# MBoardConnect.net
KiCad netlist of a schematic drawn in Altium Designer
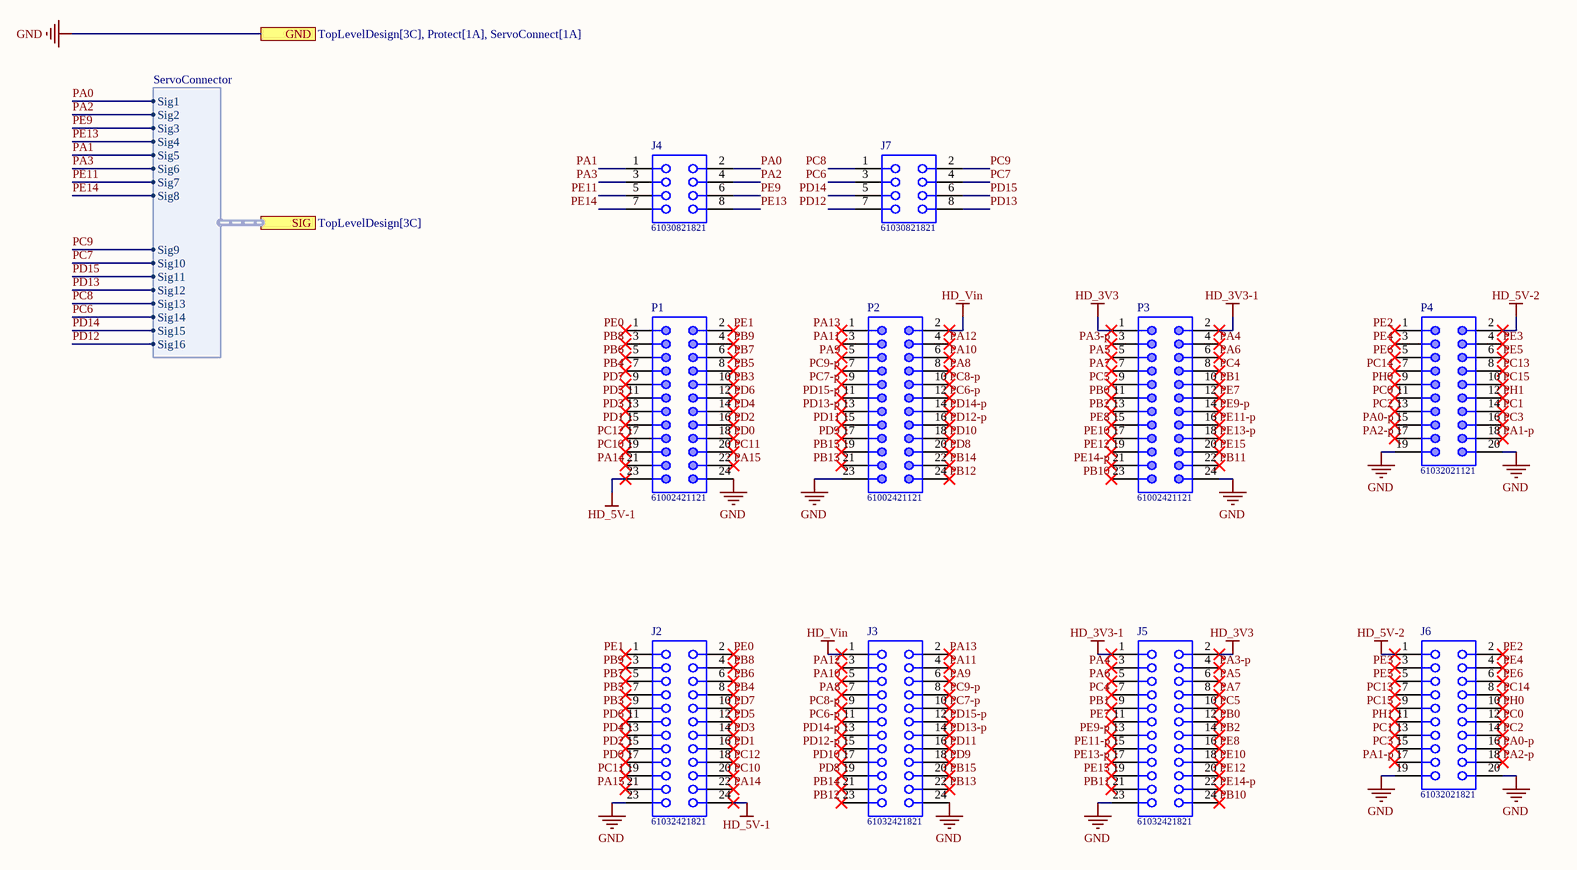
[diagram p0: MBoardConnect.SchDoc]

(export (version "E")
  (design (tool "Eeschema 10.0.6"))
  (components
    (comp (ref "J2")
      (value "61032421821")
      (footprint "61032421821")
      (description "WR-PHD Socket Header, SMT, pitch 2.54mm, Dual Row, Vertical, 24p")
      (fields (field (name "MANUFACTURER") "Wurth Elektronik"))
      (libsource (lib "Tin Tran") (part "613024243121"))
    )
    (comp (ref "J3")
      (value "61032421821")
      (footprint "61032421821")
      (description "WR-PHD Socket Header, SMT, pitch 2.54mm, Dual Row, Vertical, 24p")
      (fields (field (name "MANUFACTURER") "Wurth Elektronik"))
      (libsource (lib "Tin Tran") (part "613024243121"))
    )
    (comp (ref "J4")
      (value "61030821821")
      (footprint "61030821821")
      (description "WR-PHD Socket Header, SMT, pitch 2.54mm, Dual Row, Vertical, 8p")
      (fields (field (name "MANUFACTURER") "Wurth Elektronik"))
      (libsource (lib "Tin Tran") (part "613008243121"))
    )
    (comp (ref "J5")
      (value "61032421821")
      (footprint "61032421821")
      (description "WR-PHD Socket Header, SMT, pitch 2.54mm, Dual Row, Vertical, 24p")
      (fields (field (name "MANUFACTURER") "Wurth Elektronik"))
      (libsource (lib "Tin Tran") (part "613024243121"))
    )
    (comp (ref "J6")
      (value "61032021821")
      (footprint "61032021821")
      (description "WR-PHD Socket Header, SMT, pitch 2.54mm, Dual Row, Vertical, 20p")
      (fields (field (name "MANUFACTURER") "Wurth Elektronik"))
      (libsource (lib "Tin Tran") (part "613020243121"))
    )
    (comp (ref "J7")
      (value "61030821821")
      (footprint "61030821821")
      (description "WR-PHD Socket Header, SMT, pitch 2.54mm, Dual Row, Vertical, 8p")
      (fields (field (name "MANUFACTURER") "Wurth Elektronik"))
      (libsource (lib "Tin Tran") (part "613008243121"))
    )
    (comp (ref "P1")
      (value "61002421121")
      (footprint "61002421121")
      (description "WR-PHD Pin Header, SMT, pitch 2.54mm, Dual Row, Vertical, 24p")
      (fields (field (name "MANUFACTURER") "Wurth Elektronik"))
      (libsource (lib "Tin Tran") (part "61302421121"))
    )
    (comp (ref "P2")
      (value "61002421121")
      (footprint "61002421121")
      (description "WR-PHD Pin Header, SMT, pitch 2.54mm, Dual Row, Vertical, 24p")
      (fields (field (name "MANUFACTURER") "Wurth Elektronik"))
      (libsource (lib "Tin Tran") (part "61302421121"))
    )
    (comp (ref "P3")
      (value "61002421121")
      (footprint "61002421121")
      (description "WR-PHD Pin Header, SMT, pitch 2.54mm, Dual Row, Vertical, 24p")
      (fields (field (name "MANUFACTURER") "Wurth Elektronik"))
      (libsource (lib "Tin Tran") (part "61302421121"))
    )
    (comp (ref "P4")
      (value "61032021121")
      (footprint "61032021121")
      (description "WR-PHD Pin Header, SMT, pitch 2.54mm, Dual Row, Vertical, 20p")
      (fields (field (name "MANUFACTURER") "Wurth Elektronik"))
      (libsource (lib "Tin Tran") (part "61302021121"))
    )
  )
  (nets
    (net (code "2") (name "/PA0") (class "Default")
      (node (ref "J4") (pin "2") (pinfunction "2_2") (pintype "passive"))
    )
    (net (code "3") (name "/PA0-p") (class "Default")
      (node (ref "J6") (pin "16") (pinfunction "16_16") (pintype "passive"))
      (node (ref "P4") (pin "15") (pinfunction "15_15") (pintype "passive"))
    )
    (net (code "4") (name "/PA1") (class "Default")
      (node (ref "J4") (pin "1") (pinfunction "1_1") (pintype "passive"))
    )
    (net (code "5") (name "/PA1-p") (class "Default")
      (node (ref "J6") (pin "17") (pinfunction "17_17") (pintype "passive"))
      (node (ref "P4") (pin "18") (pinfunction "18_18") (pintype "passive"))
    )
    (net (code "6") (name "/PA2") (class "Default")
      (node (ref "J4") (pin "4") (pinfunction "4_4") (pintype "passive"))
    )
    (net (code "7") (name "/PA2-p") (class "Default")
      (node (ref "J6") (pin "18") (pinfunction "18_18") (pintype "passive"))
      (node (ref "P4") (pin "17") (pinfunction "17_17") (pintype "passive"))
    )
    (net (code "8") (name "/PA3") (class "Default")
      (node (ref "J4") (pin "3") (pinfunction "3_3") (pintype "passive"))
    )
    (net (code "9") (name "/PA3-p") (class "Default")
      (node (ref "J5") (pin "4") (pinfunction "4_4") (pintype "passive"))
      (node (ref "P3") (pin "3") (pinfunction "3_3") (pintype "passive"))
    )
    (net (code "10") (name "/PA4") (class "Default")
      (node (ref "J5") (pin "3") (pinfunction "3_3") (pintype "passive"))
      (node (ref "P3") (pin "4") (pinfunction "4_4") (pintype "passive"))
    )
    (net (code "11") (name "/PA5") (class "Default")
      (node (ref "J5") (pin "6") (pinfunction "6_6") (pintype "passive"))
      (node (ref "P3") (pin "5") (pinfunction "5_5") (pintype "passive"))
    )
    (net (code "12") (name "/PA6") (class "Default")
      (node (ref "J5") (pin "5") (pinfunction "5_5") (pintype "passive"))
      (node (ref "P3") (pin "6") (pinfunction "6_6") (pintype "passive"))
    )
    (net (code "13") (name "/PA7") (class "Default")
      (node (ref "J5") (pin "8") (pinfunction "8_8") (pintype "passive"))
      (node (ref "P3") (pin "7") (pinfunction "7_7") (pintype "passive"))
    )
    (net (code "14") (name "/PA8") (class "Default")
      (node (ref "J3") (pin "7") (pinfunction "7_7") (pintype "passive"))
      (node (ref "P2") (pin "8") (pinfunction "8_8") (pintype "passive"))
    )
    (net (code "15") (name "/PA9") (class "Default")
      (node (ref "J3") (pin "6") (pinfunction "6_6") (pintype "passive"))
      (node (ref "P2") (pin "5") (pinfunction "5_5") (pintype "passive"))
    )
    (net (code "16") (name "/PA10") (class "Default")
      (node (ref "J3") (pin "5") (pinfunction "5_5") (pintype "passive"))
      (node (ref "P2") (pin "6") (pinfunction "6_6") (pintype "passive"))
    )
    (net (code "17") (name "/PA11") (class "Default")
      (node (ref "J3") (pin "4") (pinfunction "4_4") (pintype "passive"))
      (node (ref "P2") (pin "3") (pinfunction "3_3") (pintype "passive"))
    )
    (net (code "18") (name "/PA12") (class "Default")
      (node (ref "J3") (pin "3") (pinfunction "3_3") (pintype "passive"))
      (node (ref "P2") (pin "4") (pinfunction "4_4") (pintype "passive"))
    )
    (net (code "19") (name "/PA13") (class "Default")
      (node (ref "J3") (pin "2") (pinfunction "2_2") (pintype "passive"))
      (node (ref "P2") (pin "1") (pinfunction "1_1") (pintype "passive"))
    )
    (net (code "20") (name "/PA14") (class "Default")
      (node (ref "J2") (pin "22") (pinfunction "22_22") (pintype "passive"))
      (node (ref "P1") (pin "21") (pinfunction "21_21") (pintype "passive"))
    )
    (net (code "21") (name "/PA15") (class "Default")
      (node (ref "J2") (pin "21") (pinfunction "21_21") (pintype "passive"))
      (node (ref "P1") (pin "22") (pinfunction "22_22") (pintype "passive"))
    )
    (net (code "22") (name "/PB0") (class "Default")
      (node (ref "J5") (pin "12") (pinfunction "12_12") (pintype "passive"))
      (node (ref "P3") (pin "11") (pinfunction "11_11") (pintype "passive"))
    )
    (net (code "23") (name "/PB1") (class "Default")
      (node (ref "J5") (pin "9") (pinfunction "9_9") (pintype "passive"))
      (node (ref "P3") (pin "10") (pinfunction "10_10") (pintype "passive"))
    )
    (net (code "24") (name "/PB2") (class "Default")
      (node (ref "J5") (pin "14") (pinfunction "14_14") (pintype "passive"))
      (node (ref "P3") (pin "13") (pinfunction "13_13") (pintype "passive"))
    )
    (net (code "25") (name "/PB3") (class "Default")
      (node (ref "J2") (pin "9") (pinfunction "9_9") (pintype "passive"))
      (node (ref "P1") (pin "10") (pinfunction "10_10") (pintype "passive"))
    )
    (net (code "26") (name "/PB4") (class "Default")
      (node (ref "J2") (pin "8") (pinfunction "8_8") (pintype "passive"))
      (node (ref "P1") (pin "7") (pinfunction "7_7") (pintype "passive"))
    )
    (net (code "27") (name "/PB5") (class "Default")
      (node (ref "J2") (pin "7") (pinfunction "7_7") (pintype "passive"))
      (node (ref "P1") (pin "8") (pinfunction "8_8") (pintype "passive"))
    )
    (net (code "28") (name "/PB6") (class "Default")
      (node (ref "J2") (pin "6") (pinfunction "6_6") (pintype "passive"))
      (node (ref "P1") (pin "5") (pinfunction "5_5") (pintype "passive"))
    )
    (net (code "29") (name "/PB7") (class "Default")
      (node (ref "J2") (pin "5") (pinfunction "5_5") (pintype "passive"))
      (node (ref "P1") (pin "6") (pinfunction "6_6") (pintype "passive"))
    )
    (net (code "30") (name "/PB8") (class "Default")
      (node (ref "J2") (pin "4") (pinfunction "4_4") (pintype "passive"))
      (node (ref "P1") (pin "3") (pinfunction "3_3") (pintype "passive"))
    )
    (net (code "31") (name "/PB9") (class "Default")
      (node (ref "J2") (pin "3") (pinfunction "3_3") (pintype "passive"))
      (node (ref "P1") (pin "4") (pinfunction "4_4") (pintype "passive"))
    )
    (net (code "32") (name "/PB10") (class "Default")
      (node (ref "J5") (pin "24") (pinfunction "24_24") (pintype "passive"))
      (node (ref "P3") (pin "23") (pinfunction "23_23") (pintype "passive"))
    )
    (net (code "33") (name "/PB11") (class "Default")
      (node (ref "J5") (pin "21") (pinfunction "21_21") (pintype "passive"))
      (node (ref "P3") (pin "22") (pinfunction "22_22") (pintype "passive"))
    )
    (net (code "34") (name "/PB12") (class "Default")
      (node (ref "J3") (pin "23") (pinfunction "23_23") (pintype "passive"))
      (node (ref "P2") (pin "24") (pinfunction "24_24") (pintype "passive"))
    )
    (net (code "35") (name "/PB13") (class "Default")
      (node (ref "J3") (pin "22") (pinfunction "22_22") (pintype "passive"))
      (node (ref "P2") (pin "21") (pinfunction "21_21") (pintype "passive"))
    )
    (net (code "36") (name "/PB14") (class "Default")
      (node (ref "J3") (pin "21") (pinfunction "21_21") (pintype "passive"))
      (node (ref "P2") (pin "22") (pinfunction "22_22") (pintype "passive"))
    )
    (net (code "37") (name "/PB15") (class "Default")
      (node (ref "J3") (pin "20") (pinfunction "20_20") (pintype "passive"))
      (node (ref "P2") (pin "19") (pinfunction "19_19") (pintype "passive"))
    )
    (net (code "38") (name "/PC0") (class "Default")
      (node (ref "J6") (pin "12") (pinfunction "12_12") (pintype "passive"))
      (node (ref "P4") (pin "11") (pinfunction "11_11") (pintype "passive"))
    )
    (net (code "39") (name "/PC1") (class "Default")
      (node (ref "J6") (pin "13") (pinfunction "13_13") (pintype "passive"))
      (node (ref "P4") (pin "14") (pinfunction "14_14") (pintype "passive"))
    )
    (net (code "40") (name "/PC2") (class "Default")
      (node (ref "J6") (pin "14") (pinfunction "14_14") (pintype "passive"))
      (node (ref "P4") (pin "13") (pinfunction "13_13") (pintype "passive"))
    )
    (net (code "41") (name "/PC3") (class "Default")
      (node (ref "J6") (pin "15") (pinfunction "15_15") (pintype "passive"))
      (node (ref "P4") (pin "16") (pinfunction "16_16") (pintype "passive"))
    )
    (net (code "42") (name "/PC4") (class "Default")
      (node (ref "J5") (pin "7") (pinfunction "7_7") (pintype "passive"))
      (node (ref "P3") (pin "8") (pinfunction "8_8") (pintype "passive"))
    )
    (net (code "43") (name "/PC5") (class "Default")
      (node (ref "J5") (pin "10") (pinfunction "10_10") (pintype "passive"))
      (node (ref "P3") (pin "9") (pinfunction "9_9") (pintype "passive"))
    )
    (net (code "44") (name "/PC6") (class "Default")
      (node (ref "J7") (pin "3") (pinfunction "3_3") (pintype "passive"))
    )
    (net (code "45") (name "/PC6-p") (class "Default")
      (node (ref "J3") (pin "11") (pinfunction "11_11") (pintype "passive"))
      (node (ref "P2") (pin "12") (pinfunction "12_12") (pintype "passive"))
    )
    (net (code "46") (name "/PC7") (class "Default")
      (node (ref "J7") (pin "4") (pinfunction "4_4") (pintype "passive"))
    )
    (net (code "47") (name "/PC7-p") (class "Default")
      (node (ref "J3") (pin "10") (pinfunction "10_10") (pintype "passive"))
      (node (ref "P2") (pin "9") (pinfunction "9_9") (pintype "passive"))
    )
    (net (code "48") (name "/PC8") (class "Default")
      (node (ref "J7") (pin "1") (pinfunction "1_1") (pintype "passive"))
    )
    (net (code "49") (name "/PC8-p") (class "Default")
      (node (ref "J3") (pin "9") (pinfunction "9_9") (pintype "passive"))
      (node (ref "P2") (pin "10") (pinfunction "10_10") (pintype "passive"))
    )
    (net (code "50") (name "/PC9") (class "Default")
      (node (ref "J7") (pin "2") (pinfunction "2_2") (pintype "passive"))
    )
    (net (code "51") (name "/PC9-p") (class "Default")
      (node (ref "J3") (pin "8") (pinfunction "8_8") (pintype "passive"))
      (node (ref "P2") (pin "7") (pinfunction "7_7") (pintype "passive"))
    )
    (net (code "52") (name "/PC10") (class "Default")
      (node (ref "J2") (pin "20") (pinfunction "20_20") (pintype "passive"))
      (node (ref "P1") (pin "19") (pinfunction "19_19") (pintype "passive"))
    )
    (net (code "53") (name "/PC11") (class "Default")
      (node (ref "J2") (pin "19") (pinfunction "19_19") (pintype "passive"))
      (node (ref "P1") (pin "20") (pinfunction "20_20") (pintype "passive"))
    )
    (net (code "54") (name "/PC12") (class "Default")
      (node (ref "J2") (pin "18") (pinfunction "18_18") (pintype "passive"))
      (node (ref "P1") (pin "17") (pinfunction "17_17") (pintype "passive"))
    )
    (net (code "55") (name "/PC13") (class "Default")
      (node (ref "J6") (pin "7") (pinfunction "7_7") (pintype "passive"))
      (node (ref "P4") (pin "8") (pinfunction "8_8") (pintype "passive"))
    )
    (net (code "56") (name "/PC14") (class "Default")
      (node (ref "J6") (pin "8") (pinfunction "8_8") (pintype "passive"))
      (node (ref "P4") (pin "7") (pinfunction "7_7") (pintype "passive"))
    )
    (net (code "57") (name "/PC15") (class "Default")
      (node (ref "J6") (pin "9") (pinfunction "9_9") (pintype "passive"))
      (node (ref "P4") (pin "10") (pinfunction "10_10") (pintype "passive"))
    )
    (net (code "58") (name "/PD0") (class "Default")
      (node (ref "J2") (pin "17") (pinfunction "17_17") (pintype "passive"))
      (node (ref "P1") (pin "18") (pinfunction "18_18") (pintype "passive"))
    )
    (net (code "59") (name "/PD1") (class "Default")
      (node (ref "J2") (pin "16") (pinfunction "16_16") (pintype "passive"))
      (node (ref "P1") (pin "15") (pinfunction "15_15") (pintype "passive"))
    )
    (net (code "60") (name "/PD2") (class "Default")
      (node (ref "J2") (pin "15") (pinfunction "15_15") (pintype "passive"))
      (node (ref "P1") (pin "16") (pinfunction "16_16") (pintype "passive"))
    )
    (net (code "61") (name "/PD3") (class "Default")
      (node (ref "J2") (pin "14") (pinfunction "14_14") (pintype "passive"))
      (node (ref "P1") (pin "13") (pinfunction "13_13") (pintype "passive"))
    )
    (net (code "62") (name "/PD4") (class "Default")
      (node (ref "J2") (pin "13") (pinfunction "13_13") (pintype "passive"))
      (node (ref "P1") (pin "14") (pinfunction "14_14") (pintype "passive"))
    )
    (net (code "63") (name "/PD5") (class "Default")
      (node (ref "J2") (pin "12") (pinfunction "12_12") (pintype "passive"))
      (node (ref "P1") (pin "11") (pinfunction "11_11") (pintype "passive"))
    )
    (net (code "64") (name "/PD6") (class "Default")
      (node (ref "J2") (pin "11") (pinfunction "11_11") (pintype "passive"))
      (node (ref "P1") (pin "12") (pinfunction "12_12") (pintype "passive"))
    )
    (net (code "65") (name "/PD7") (class "Default")
      (node (ref "J2") (pin "10") (pinfunction "10_10") (pintype "passive"))
      (node (ref "P1") (pin "9") (pinfunction "9_9") (pintype "passive"))
    )
    (net (code "66") (name "/PD8") (class "Default")
      (node (ref "J3") (pin "19") (pinfunction "19_19") (pintype "passive"))
      (node (ref "P2") (pin "20") (pinfunction "20_20") (pintype "passive"))
    )
    (net (code "67") (name "/PD9") (class "Default")
      (node (ref "J3") (pin "18") (pinfunction "18_18") (pintype "passive"))
      (node (ref "P2") (pin "17") (pinfunction "17_17") (pintype "passive"))
    )
    (net (code "68") (name "/PD10") (class "Default")
      (node (ref "J3") (pin "17") (pinfunction "17_17") (pintype "passive"))
      (node (ref "P2") (pin "18") (pinfunction "18_18") (pintype "passive"))
    )
    (net (code "69") (name "/PD11") (class "Default")
      (node (ref "J3") (pin "16") (pinfunction "16_16") (pintype "passive"))
      (node (ref "P2") (pin "15") (pinfunction "15_15") (pintype "passive"))
    )
    (net (code "70") (name "/PD12") (class "Default")
      (node (ref "J7") (pin "7") (pinfunction "7_7") (pintype "passive"))
    )
    (net (code "71") (name "/PD12-p") (class "Default")
      (node (ref "J3") (pin "15") (pinfunction "15_15") (pintype "passive"))
      (node (ref "P2") (pin "16") (pinfunction "16_16") (pintype "passive"))
    )
    (net (code "72") (name "/PD13") (class "Default")
      (node (ref "J7") (pin "8") (pinfunction "8_8") (pintype "passive"))
    )
    (net (code "73") (name "/PD13-p") (class "Default")
      (node (ref "J3") (pin "14") (pinfunction "14_14") (pintype "passive"))
      (node (ref "P2") (pin "13") (pinfunction "13_13") (pintype "passive"))
    )
    (net (code "74") (name "/PD14") (class "Default")
      (node (ref "J7") (pin "5") (pinfunction "5_5") (pintype "passive"))
    )
    (net (code "75") (name "/PD14-p") (class "Default")
      (node (ref "J3") (pin "13") (pinfunction "13_13") (pintype "passive"))
      (node (ref "P2") (pin "14") (pinfunction "14_14") (pintype "passive"))
    )
    (net (code "76") (name "/PD15") (class "Default")
      (node (ref "J7") (pin "6") (pinfunction "6_6") (pintype "passive"))
    )
    (net (code "77") (name "/PD15-p") (class "Default")
      (node (ref "J3") (pin "12") (pinfunction "12_12") (pintype "passive"))
      (node (ref "P2") (pin "11") (pinfunction "11_11") (pintype "passive"))
    )
    (net (code "78") (name "/PE0") (class "Default")
      (node (ref "J2") (pin "2") (pinfunction "2_2") (pintype "passive"))
      (node (ref "P1") (pin "1") (pinfunction "1_1") (pintype "passive"))
    )
    (net (code "79") (name "/PE1") (class "Default")
      (node (ref "J2") (pin "1") (pinfunction "1_1") (pintype "passive"))
      (node (ref "P1") (pin "2") (pinfunction "2_2") (pintype "passive"))
    )
    (net (code "80") (name "/PE2") (class "Default")
      (node (ref "J6") (pin "2") (pinfunction "2_2") (pintype "passive"))
      (node (ref "P4") (pin "1") (pinfunction "1_1") (pintype "passive"))
    )
    (net (code "81") (name "/PE3") (class "Default")
      (node (ref "J6") (pin "3") (pinfunction "3_3") (pintype "passive"))
      (node (ref "P4") (pin "4") (pinfunction "4_4") (pintype "passive"))
    )
    (net (code "82") (name "/PE4") (class "Default")
      (node (ref "J6") (pin "4") (pinfunction "4_4") (pintype "passive"))
      (node (ref "P4") (pin "3") (pinfunction "3_3") (pintype "passive"))
    )
    (net (code "83") (name "/PE5") (class "Default")
      (node (ref "J6") (pin "5") (pinfunction "5_5") (pintype "passive"))
      (node (ref "P4") (pin "6") (pinfunction "6_6") (pintype "passive"))
    )
    (net (code "84") (name "/PE6") (class "Default")
      (node (ref "J6") (pin "6") (pinfunction "6_6") (pintype "passive"))
      (node (ref "P4") (pin "5") (pinfunction "5_5") (pintype "passive"))
    )
    (net (code "85") (name "/PE7") (class "Default")
      (node (ref "J5") (pin "11") (pinfunction "11_11") (pintype "passive"))
      (node (ref "P3") (pin "12") (pinfunction "12_12") (pintype "passive"))
    )
    (net (code "86") (name "/PE8") (class "Default")
      (node (ref "J5") (pin "16") (pinfunction "16_16") (pintype "passive"))
      (node (ref "P3") (pin "15") (pinfunction "15_15") (pintype "passive"))
    )
    (net (code "87") (name "/PE9") (class "Default")
      (node (ref "J4") (pin "6") (pinfunction "6_6") (pintype "passive"))
    )
    (net (code "88") (name "/PE9-p") (class "Default")
      (node (ref "J5") (pin "13") (pinfunction "13_13") (pintype "passive"))
      (node (ref "P3") (pin "14") (pinfunction "14_14") (pintype "passive"))
    )
    (net (code "89") (name "/PE10") (class "Default")
      (node (ref "J5") (pin "18") (pinfunction "18_18") (pintype "passive"))
      (node (ref "P3") (pin "17") (pinfunction "17_17") (pintype "passive"))
    )
    (net (code "90") (name "/PE11") (class "Default")
      (node (ref "J4") (pin "5") (pinfunction "5_5") (pintype "passive"))
    )
    (net (code "91") (name "/PE11-p") (class "Default")
      (node (ref "J5") (pin "15") (pinfunction "15_15") (pintype "passive"))
      (node (ref "P3") (pin "16") (pinfunction "16_16") (pintype "passive"))
    )
    (net (code "92") (name "/PE12") (class "Default")
      (node (ref "J5") (pin "20") (pinfunction "20_20") (pintype "passive"))
      (node (ref "P3") (pin "19") (pinfunction "19_19") (pintype "passive"))
    )
    (net (code "93") (name "/PE13") (class "Default")
      (node (ref "J4") (pin "8") (pinfunction "8_8") (pintype "passive"))
    )
    (net (code "94") (name "/PE13-p") (class "Default")
      (node (ref "J5") (pin "17") (pinfunction "17_17") (pintype "passive"))
      (node (ref "P3") (pin "18") (pinfunction "18_18") (pintype "passive"))
    )
    (net (code "95") (name "/PE14") (class "Default")
      (node (ref "J4") (pin "7") (pinfunction "7_7") (pintype "passive"))
    )
    (net (code "96") (name "/PE14-p") (class "Default")
      (node (ref "J5") (pin "22") (pinfunction "22_22") (pintype "passive"))
      (node (ref "P3") (pin "21") (pinfunction "21_21") (pintype "passive"))
    )
    (net (code "97") (name "/PE15") (class "Default")
      (node (ref "J5") (pin "19") (pinfunction "19_19") (pintype "passive"))
      (node (ref "P3") (pin "20") (pinfunction "20_20") (pintype "passive"))
    )
    (net (code "98") (name "/PH0") (class "Default")
      (node (ref "J6") (pin "10") (pinfunction "10_10") (pintype "passive"))
      (node (ref "P4") (pin "9") (pinfunction "9_9") (pintype "passive"))
    )
    (net (code "99") (name "/PH1") (class "Default")
      (node (ref "J6") (pin "11") (pinfunction "11_11") (pintype "passive"))
      (node (ref "P4") (pin "12") (pinfunction "12_12") (pintype "passive"))
    )
    (net (code "101") (name "GND") (class "Default")
      (node (ref "J2") (pin "23") (pinfunction "23_23") (pintype "passive"))
      (node (ref "J3") (pin "24") (pinfunction "24_24") (pintype "passive"))
      (node (ref "J5") (pin "23") (pinfunction "23_23") (pintype "passive"))
      (node (ref "J6") (pin "19") (pinfunction "19_19") (pintype "passive"))
      (node (ref "J6") (pin "20") (pinfunction "20_20") (pintype "passive"))
      (node (ref "P1") (pin "24") (pinfunction "24_24") (pintype "passive"))
      (node (ref "P2") (pin "23") (pinfunction "23_23") (pintype "passive"))
      (node (ref "P3") (pin "24") (pinfunction "24_24") (pintype "passive"))
      (node (ref "P4") (pin "19") (pinfunction "19_19") (pintype "passive"))
      (node (ref "P4") (pin "20") (pinfunction "20_20") (pintype "passive"))
    )
    (net (code "102") (name "HD_3V3") (class "Default")
      (node (ref "J5") (pin "2") (pinfunction "2_2") (pintype "passive"))
      (node (ref "P3") (pin "1") (pinfunction "1_1") (pintype "passive"))
    )
    (net (code "103") (name "HD_3V3-1") (class "Default")
      (node (ref "J5") (pin "1") (pinfunction "1_1") (pintype "passive"))
      (node (ref "P3") (pin "2") (pinfunction "2_2") (pintype "passive"))
    )
    (net (code "104") (name "HD_5V-1") (class "Default")
      (node (ref "J2") (pin "24") (pinfunction "24_24") (pintype "passive"))
      (node (ref "P1") (pin "23") (pinfunction "23_23") (pintype "passive"))
    )
    (net (code "105") (name "HD_5V-2") (class "Default")
      (node (ref "J6") (pin "1") (pinfunction "1_1") (pintype "passive"))
      (node (ref "P4") (pin "2") (pinfunction "2_2") (pintype "passive"))
    )
    (net (code "106") (name "HD_Vin") (class "Default")
      (node (ref "J3") (pin "1") (pinfunction "1_1") (pintype "passive"))
      (node (ref "P2") (pin "2") (pinfunction "2_2") (pintype "passive"))
    )
  )
)
